# SCH_I2C-themister_EasyEDA.net
KiCad netlist of a schematic drawn in EasyEDA
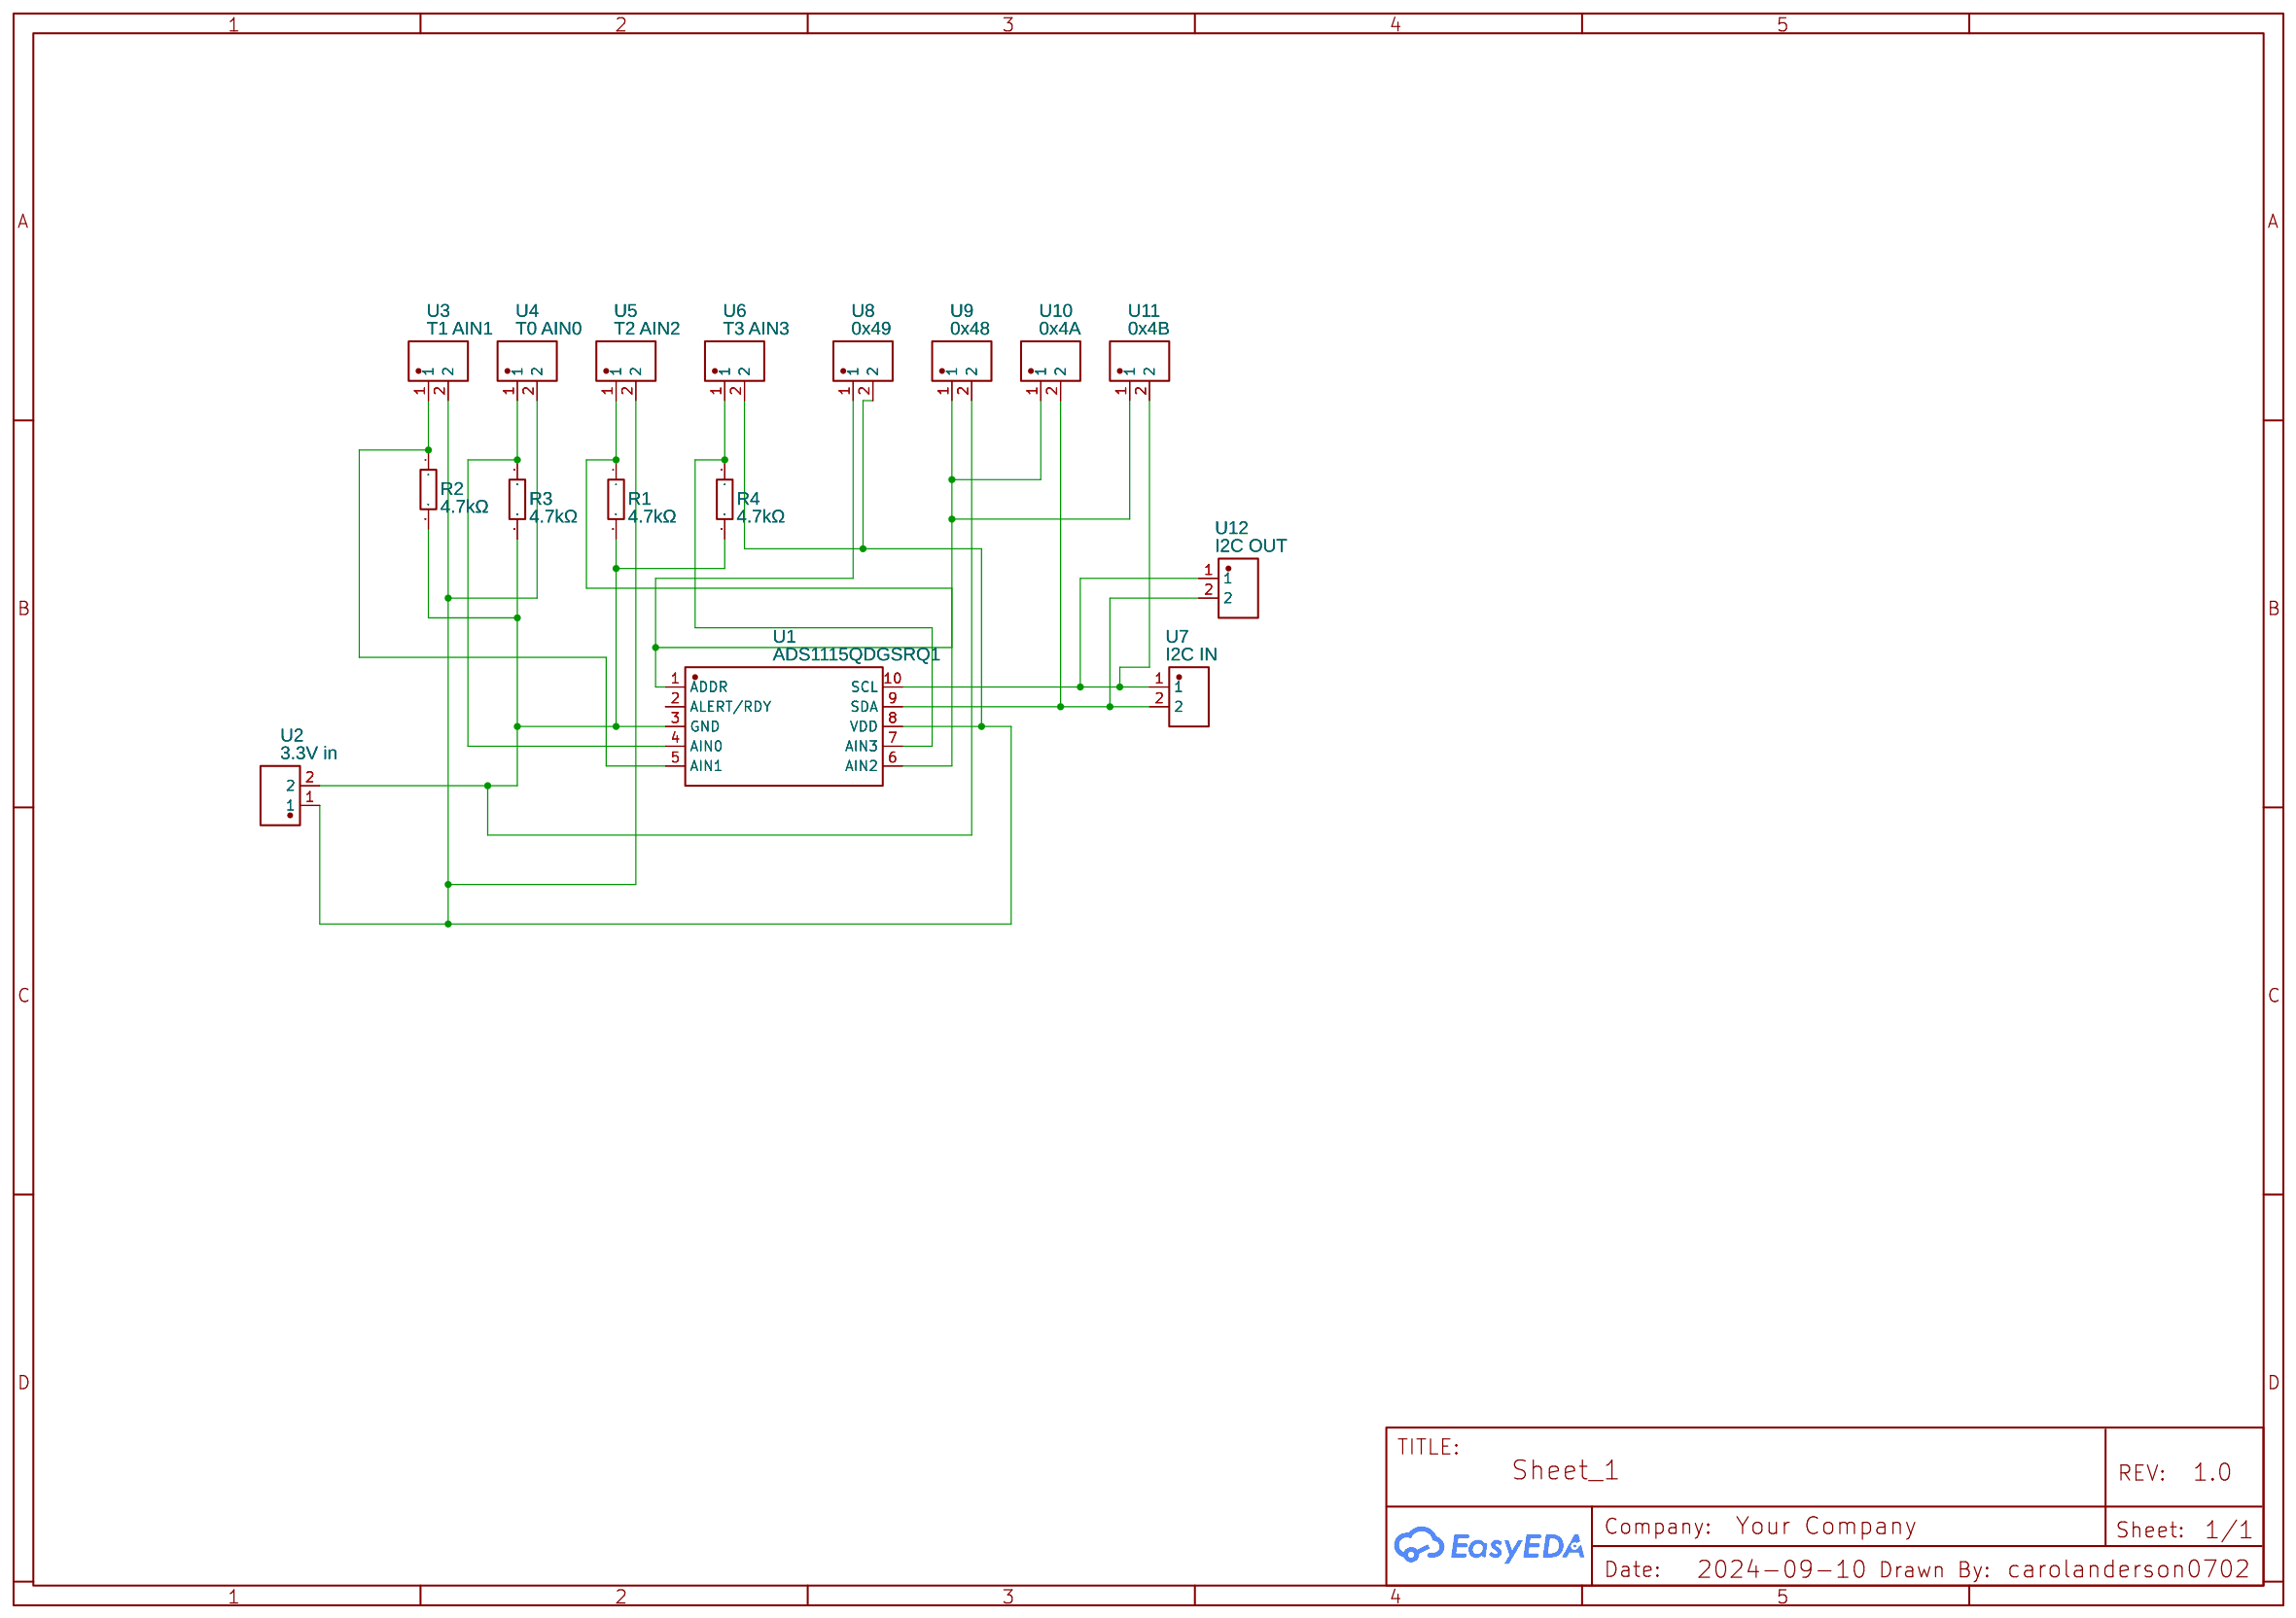
[diagram p0: schematic sheet]

(export (version "E")
  (design (tool "Eeschema 10.0.6"))
  (components
    (comp (ref "R1")
      (value "4.7kΩ")
      (fields (field (name "Manufacturer Part") "RC0603FR-074K7L") (field (name "Manufacturer") "YAGEO(国巨)"))
      (libsource (lib "") (part "RC0603FR-074K7L"))
    )
    (comp (ref "R2")
      (value "4.7kΩ")
      (fields (field (name "Manufacturer Part") "RC0603FR-074K7L") (field (name "Manufacturer") "YAGEO(国巨)"))
      (libsource (lib "") (part "RC0603FR-074K7L"))
    )
    (comp (ref "R3")
      (value "4.7kΩ")
      (fields (field (name "Manufacturer Part") "RC0603FR-074K7L") (field (name "Manufacturer") "YAGEO(国巨)"))
      (libsource (lib "") (part "RC0603FR-074K7L"))
    )
    (comp (ref "R4")
      (value "4.7kΩ")
      (fields (field (name "Manufacturer Part") "RC0603FR-074K7L") (field (name "Manufacturer") "YAGEO(国巨)"))
      (libsource (lib "") (part "RC0603FR-074K7L"))
    )
    (comp (ref "U1")
      (value "ADS1115QDGSRQ1")
      (fields (field (name "Manufacturer") "TI(德州仪器)"))
      (libsource (lib "") (part "ADS1115QDGSRQ1"))
    )
    (comp (ref "U2")
      (value "3.3V in")
      (fields (field (name "Manufacturer Part") "JL124D-38102G01") (field (name "Manufacturer") "JILN(锦凌)"))
      (libsource (lib "") (part "JL124D-38102G01"))
    )
    (comp (ref "U3")
      (value "T1 AIN1")
      (fields
        (field (name "Manufacturer Part") "ZX-PZ2.54-1-2PZZ")
        (field (name "Manufacturer") "Megastar(兆星)")
      )
      (libsource (lib "") (part "ZX-PZ2.54-1-2PZZ"))
    )
    (comp (ref "U4")
      (value "T0 AIN0")
      (fields
        (field (name "Manufacturer Part") "ZX-PZ2.54-1-2PZZ")
        (field (name "Manufacturer") "Megastar(兆星)")
      )
      (libsource (lib "") (part "ZX-PZ2.54-1-2PZZ"))
    )
    (comp (ref "U5")
      (value "T2 AIN2")
      (fields
        (field (name "Manufacturer Part") "ZX-PZ2.54-1-2PZZ")
        (field (name "Manufacturer") "Megastar(兆星)")
      )
      (libsource (lib "") (part "ZX-PZ2.54-1-2PZZ"))
    )
    (comp (ref "U6")
      (value "T3 AIN3")
      (fields
        (field (name "Manufacturer Part") "ZX-PZ2.54-1-2PZZ")
        (field (name "Manufacturer") "Megastar(兆星)")
      )
      (libsource (lib "") (part "ZX-PZ2.54-1-2PZZ"))
    )
    (comp (ref "U7")
      (value "I2C IN")
      (fields
        (field (name "Manufacturer Part") "ZX-PZ2.54-1-2PZZ")
        (field (name "Manufacturer") "Megastar(兆星)")
      )
      (libsource (lib "") (part "ZX-PZ2.54-1-2PZZ_1"))
    )
    (comp (ref "U8")
      (value "0x49")
      (fields
        (field (name "Manufacturer Part") "ZX-PZ2.54-1-2PZZ")
        (field (name "Manufacturer") "Megastar(兆星)")
      )
      (libsource (lib "") (part "ZX-PZ2.54-1-2PZZ"))
    )
    (comp (ref "U9")
      (value "0x48")
      (fields
        (field (name "Manufacturer Part") "ZX-PZ2.54-1-2PZZ")
        (field (name "Manufacturer") "Megastar(兆星)")
      )
      (libsource (lib "") (part "ZX-PZ2.54-1-2PZZ"))
    )
    (comp (ref "U10")
      (value "0x4A")
      (fields
        (field (name "Manufacturer Part") "ZX-PZ2.54-1-2PZZ")
        (field (name "Manufacturer") "Megastar(兆星)")
      )
      (libsource (lib "") (part "ZX-PZ2.54-1-2PZZ"))
    )
    (comp (ref "U11")
      (value "0x4B")
      (fields
        (field (name "Manufacturer Part") "ZX-PZ2.54-1-2PZZ")
        (field (name "Manufacturer") "Megastar(兆星)")
      )
      (libsource (lib "") (part "ZX-PZ2.54-1-2PZZ"))
    )
    (comp (ref "U12")
      (value "I2C OUT")
      (fields
        (field (name "Manufacturer Part") "ZX-PZ2.54-1-2PZZ")
        (field (name "Manufacturer") "Megastar(兆星)")
      )
      (libsource (lib "") (part "ZX-PZ2.54-1-2PZZ_1"))
    )
  )
  (nets
    (net (code "1") (name "Net-(U1-ADDR)") (class "Default")
      (node (ref "U1") (pin "1") (pinfunction "ADDR_1") (pintype "unspecified"))
      (node (ref "U10") (pin "1") (pinfunction "1_1") (pintype "unspecified"))
      (node (ref "U11") (pin "1") (pinfunction "1_1") (pintype "unspecified"))
      (node (ref "U8") (pin "1") (pinfunction "1_1") (pintype "unspecified"))
      (node (ref "U9") (pin "1") (pinfunction "1_1") (pintype "unspecified"))
    )
    (net (code "2") (name "Net-(U1-AIN0)") (class "Default")
      (node (ref "R3") (pin "1") (pinfunction "1_1") (pintype "input"))
      (node (ref "U1") (pin "4") (pinfunction "AIN0_4") (pintype "unspecified"))
      (node (ref "U4") (pin "1") (pinfunction "1_1") (pintype "unspecified"))
    )
    (net (code "3") (name "Net-(U1-AIN1)") (class "Default")
      (node (ref "R2") (pin "1") (pinfunction "1_1") (pintype "input"))
      (node (ref "U1") (pin "5") (pinfunction "AIN1_5") (pintype "unspecified"))
      (node (ref "U3") (pin "1") (pinfunction "1_1") (pintype "unspecified"))
    )
    (net (code "4") (name "Net-(U1-AIN2)") (class "Default")
      (node (ref "R1") (pin "1") (pinfunction "1_1") (pintype "input"))
      (node (ref "U1") (pin "6") (pinfunction "AIN2_6") (pintype "unspecified"))
      (node (ref "U5") (pin "1") (pinfunction "1_1") (pintype "unspecified"))
    )
    (net (code "5") (name "Net-(U1-AIN3)") (class "Default")
      (node (ref "R4") (pin "1") (pinfunction "1_1") (pintype "input"))
      (node (ref "U1") (pin "7") (pinfunction "AIN3_7") (pintype "unspecified"))
      (node (ref "U6") (pin "1") (pinfunction "1_1") (pintype "unspecified"))
    )
    (net (code "6") (name "Net-(U1-GND)") (class "Default")
      (node (ref "R1") (pin "2") (pinfunction "2_2") (pintype "input"))
      (node (ref "R2") (pin "2") (pinfunction "2_2") (pintype "input"))
      (node (ref "R3") (pin "2") (pinfunction "2_2") (pintype "input"))
      (node (ref "R4") (pin "2") (pinfunction "2_2") (pintype "input"))
      (node (ref "U1") (pin "3") (pinfunction "GND_3") (pintype "unspecified"))
      (node (ref "U2") (pin "2") (pinfunction "2_2") (pintype "unspecified"))
      (node (ref "U9") (pin "2") (pinfunction "2_2") (pintype "unspecified"))
    )
    (net (code "7") (name "Net-(U1-SCL)") (class "Default")
      (node (ref "U1") (pin "10") (pinfunction "SCL_10") (pintype "unspecified"))
      (node (ref "U11") (pin "2") (pinfunction "2_2") (pintype "unspecified"))
      (node (ref "U12") (pin "1") (pinfunction "1_1") (pintype "unspecified"))
      (node (ref "U7") (pin "1") (pinfunction "1_1") (pintype "unspecified"))
    )
    (net (code "8") (name "Net-(U1-SDA)") (class "Default")
      (node (ref "U1") (pin "9") (pinfunction "SDA_9") (pintype "unspecified"))
      (node (ref "U10") (pin "2") (pinfunction "2_2") (pintype "unspecified"))
      (node (ref "U12") (pin "2") (pinfunction "2_2") (pintype "unspecified"))
      (node (ref "U7") (pin "2") (pinfunction "2_2") (pintype "unspecified"))
    )
    (net (code "9") (name "Net-(U1-VDD)") (class "Default")
      (node (ref "U1") (pin "8") (pinfunction "VDD_8") (pintype "unspecified"))
      (node (ref "U2") (pin "1") (pinfunction "1_1") (pintype "unspecified"))
      (node (ref "U3") (pin "2") (pinfunction "2_2") (pintype "unspecified"))
      (node (ref "U4") (pin "2") (pinfunction "2_2") (pintype "unspecified"))
      (node (ref "U5") (pin "2") (pinfunction "2_2") (pintype "unspecified"))
      (node (ref "U6") (pin "2") (pinfunction "2_2") (pintype "unspecified"))
      (node (ref "U8") (pin "2") (pinfunction "2_2") (pintype "unspecified"))
    )
    (net (code "10") (name "unconnected-(U1-ALERT{slash}RDY-Pad2)") (class "Default")
      (node (ref "U1") (pin "2") (pinfunction "ALERT/RDY_2") (pintype "unspecified"))
    )
  )
)
